# tec_controller_v1.net
KiCad netlist of a schematic drawn in EAGLE
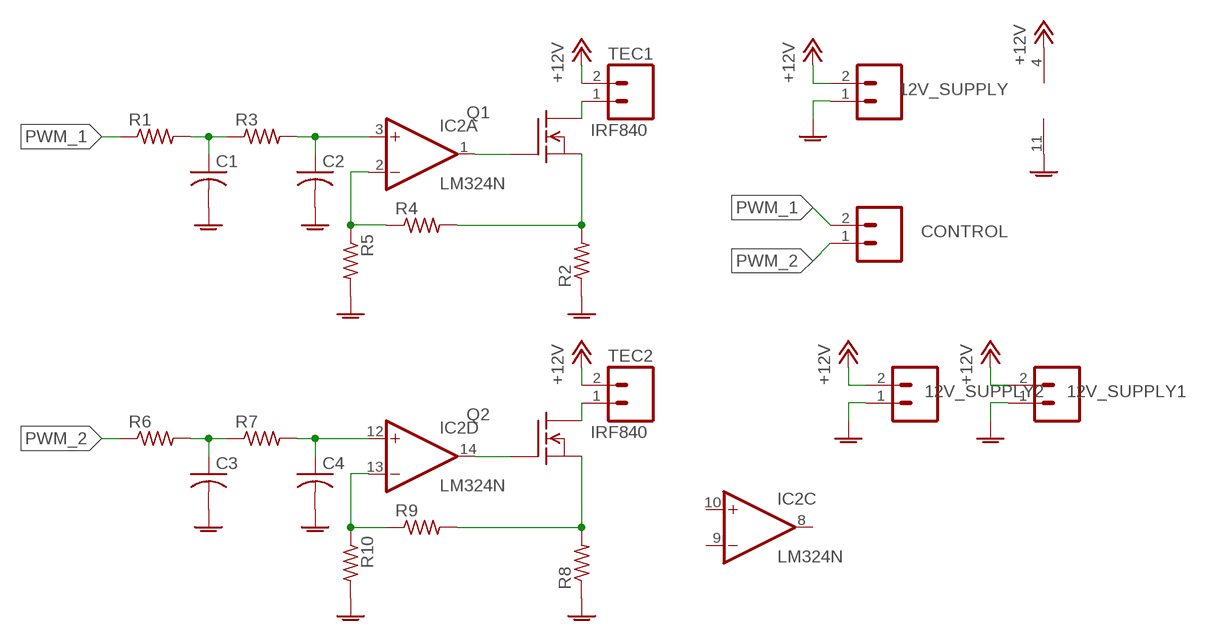
[diagram p0: schematic, sheet 1]

(export (version "E")
  (design (tool "Eeschema 10.0.6"))
  (components
    (comp (ref "12V_SUPPLY")
      (value "M02LOCK_LONGPADS")
      (footprint "eagle-import:1X02_LOCK_LONGPADS")
      (libsource (lib "eagle-import") (part "M02LOCK_LONGPADS"))
    )
    (comp (ref "12V_SUPPLY1")
      (value "M02LOCK_LONGPADS")
      (footprint "eagle-import:1X02_LOCK_LONGPADS")
      (libsource (lib "eagle-import") (part "M02LOCK_LONGPADS"))
    )
    (comp (ref "12V_SUPPLY2")
      (value "M02LOCK_LONGPADS")
      (footprint "eagle-import:1X02_LOCK_LONGPADS")
      (libsource (lib "eagle-import") (part "M02LOCK_LONGPADS"))
    )
    (comp (ref "C1")
      (value "C-USC0805")
      (footprint "eagle-import:C0805")
      (libsource (lib "eagle-import") (part "C-USC0805"))
    )
    (comp (ref "C2")
      (value "C-USC0805")
      (footprint "eagle-import:C0805")
      (libsource (lib "eagle-import") (part "C-USC0805"))
    )
    (comp (ref "C3")
      (value "C-USC0805")
      (footprint "eagle-import:C0805")
      (libsource (lib "eagle-import") (part "C-USC0805"))
    )
    (comp (ref "C4")
      (value "C-USC0805")
      (footprint "eagle-import:C0805")
      (libsource (lib "eagle-import") (part "C-USC0805"))
    )
    (comp (ref "CONTROL")
      (value "M02LOCK_LONGPADS")
      (footprint "eagle-import:1X02_LOCK_LONGPADS")
      (libsource (lib "eagle-import") (part "M02LOCK_LONGPADS"))
    )
    (comp (ref "IC2")
      (value "LM324N")
      (footprint "eagle-import:DIL14")
      (libsource (lib "eagle-import") (part "LM324N"))
    )
    (comp (ref "Q1")
      (value "IRF840")
      (footprint "eagle-import:TO220")
      (libsource (lib "eagle-import") (part "IRF840"))
    )
    (comp (ref "Q2")
      (value "IRF840")
      (footprint "eagle-import:TO220")
      (libsource (lib "eagle-import") (part "IRF840"))
    )
    (comp (ref "R1")
      (value "R-US_M0805")
      (footprint "eagle-import:M0805")
      (libsource (lib "eagle-import") (part "R-US_M0805"))
    )
    (comp (ref "R2")
      (value "R-US_V235/17")
      (footprint "eagle-import:V235_17")
      (libsource (lib "eagle-import") (part "R-US_V235/17"))
    )
    (comp (ref "R3")
      (value "R-US_M0805")
      (footprint "eagle-import:M0805")
      (libsource (lib "eagle-import") (part "R-US_M0805"))
    )
    (comp (ref "R4")
      (value "R-US_M0805")
      (footprint "eagle-import:M0805")
      (libsource (lib "eagle-import") (part "R-US_M0805"))
    )
    (comp (ref "R5")
      (value "R-US_M0805")
      (footprint "eagle-import:M0805")
      (libsource (lib "eagle-import") (part "R-US_M0805"))
    )
    (comp (ref "R6")
      (value "R-US_M0805")
      (footprint "eagle-import:M0805")
      (libsource (lib "eagle-import") (part "R-US_M0805"))
    )
    (comp (ref "R7")
      (value "R-US_M0805")
      (footprint "eagle-import:M0805")
      (libsource (lib "eagle-import") (part "R-US_M0805"))
    )
    (comp (ref "R8")
      (value "R-US_V235/17")
      (footprint "eagle-import:V235_17")
      (libsource (lib "eagle-import") (part "R-US_V235/17"))
    )
    (comp (ref "R9")
      (value "R-US_M0805")
      (footprint "eagle-import:M0805")
      (libsource (lib "eagle-import") (part "R-US_M0805"))
    )
    (comp (ref "R10")
      (value "R-US_M0805")
      (footprint "eagle-import:M0805")
      (libsource (lib "eagle-import") (part "R-US_M0805"))
    )
    (comp (ref "TEC1")
      (value "M02LOCK_LONGPADS")
      (footprint "eagle-import:1X02_LOCK_LONGPADS")
      (libsource (lib "eagle-import") (part "M02LOCK_LONGPADS"))
    )
    (comp (ref "TEC2")
      (value "M02LOCK_LONGPADS")
      (footprint "eagle-import:1X02_LOCK_LONGPADS")
      (libsource (lib "eagle-import") (part "M02LOCK_LONGPADS"))
    )
  )
  (nets
    (net (code "1") (name "+12V") (class "Default")
      (node (ref "12V_SUPPLY") (pin "2") (pinfunction "2_2") (pintype "passive"))
      (node (ref "12V_SUPPLY1") (pin "2") (pinfunction "2_2") (pintype "passive"))
      (node (ref "12V_SUPPLY2") (pin "2") (pinfunction "2_2") (pintype "passive"))
      (node (ref "IC2") (pin "4") (pinfunction "V+_4") (pintype "power_in"))
      (node (ref "TEC1") (pin "2") (pinfunction "2_2") (pintype "passive"))
      (node (ref "TEC2") (pin "2") (pinfunction "2_2") (pintype "passive"))
    )
    (net (code "2") (name "GNDA") (class "Default")
      (node (ref "12V_SUPPLY") (pin "1") (pinfunction "1_1") (pintype "passive"))
      (node (ref "12V_SUPPLY1") (pin "1") (pinfunction "1_1") (pintype "passive"))
      (node (ref "12V_SUPPLY2") (pin "1") (pinfunction "1_1") (pintype "passive"))
      (node (ref "C1") (pin "2") (pinfunction "2_2") (pintype "passive"))
      (node (ref "C2") (pin "2") (pinfunction "2_2") (pintype "passive"))
      (node (ref "C3") (pin "2") (pinfunction "2_2") (pintype "passive"))
      (node (ref "C4") (pin "2") (pinfunction "2_2") (pintype "passive"))
      (node (ref "IC2") (pin "11") (pinfunction "V-_11") (pintype "power_in"))
      (node (ref "R10") (pin "2") (pinfunction "2_2") (pintype "passive"))
      (node (ref "R2") (pin "1") (pinfunction "1_1") (pintype "passive"))
      (node (ref "R5") (pin "2") (pinfunction "2_2") (pintype "passive"))
      (node (ref "R8") (pin "1") (pinfunction "1_1") (pintype "passive"))
    )
    (net (code "3") (name "Net-(C1-Pad1)") (class "Default")
      (node (ref "C1") (pin "1") (pinfunction "1_1") (pintype "passive"))
      (node (ref "R1") (pin "2") (pinfunction "2_2") (pintype "passive"))
      (node (ref "R3") (pin "1") (pinfunction "1_1") (pintype "passive"))
    )
    (net (code "4") (name "Net-(C3-Pad1)") (class "Default")
      (node (ref "C3") (pin "1") (pinfunction "1_1") (pintype "passive"))
      (node (ref "R6") (pin "2") (pinfunction "2_2") (pintype "passive"))
      (node (ref "R7") (pin "1") (pinfunction "1_1") (pintype "passive"))
    )
    (net (code "5") (name "Net-(IC2A-+IN)") (class "Default")
      (node (ref "C2") (pin "1") (pinfunction "1_1") (pintype "passive"))
      (node (ref "IC2") (pin "3") (pinfunction "+IN_3") (pintype "input"))
      (node (ref "R3") (pin "2") (pinfunction "2_2") (pintype "passive"))
    )
    (net (code "6") (name "Net-(IC2A--IN)") (class "Default")
      (node (ref "IC2") (pin "2") (pinfunction "-IN_2") (pintype "input"))
      (node (ref "R4") (pin "1") (pinfunction "1_1") (pintype "passive"))
      (node (ref "R5") (pin "1") (pinfunction "1_1") (pintype "passive"))
    )
    (net (code "7") (name "Net-(IC2A-OUT)") (class "Default")
      (node (ref "IC2") (pin "1") (pinfunction "OUT_1") (pintype "output"))
      (node (ref "Q1") (pin "1") (pinfunction "G_1") (pintype "passive"))
    )
    (net (code "8") (name "Net-(IC2D-+IN)") (class "Default")
      (node (ref "C4") (pin "1") (pinfunction "1_1") (pintype "passive"))
      (node (ref "IC2") (pin "12") (pinfunction "+IN_12") (pintype "input"))
      (node (ref "R7") (pin "2") (pinfunction "2_2") (pintype "passive"))
    )
    (net (code "9") (name "Net-(IC2D--IN)") (class "Default")
      (node (ref "IC2") (pin "13") (pinfunction "-IN_13") (pintype "input"))
      (node (ref "R10") (pin "1") (pinfunction "1_1") (pintype "passive"))
      (node (ref "R9") (pin "1") (pinfunction "1_1") (pintype "passive"))
    )
    (net (code "10") (name "Net-(IC2D-OUT)") (class "Default")
      (node (ref "IC2") (pin "14") (pinfunction "OUT_14") (pintype "output"))
      (node (ref "Q2") (pin "1") (pinfunction "G_1") (pintype "passive"))
    )
    (net (code "11") (name "Net-(Q1-D)") (class "Default")
      (node (ref "Q1") (pin "2") (pinfunction "D_2") (pintype "passive"))
      (node (ref "TEC1") (pin "1") (pinfunction "1_1") (pintype "passive"))
    )
    (net (code "12") (name "Net-(Q1-S)") (class "Default")
      (node (ref "Q1") (pin "3") (pinfunction "S_3") (pintype "passive"))
      (node (ref "R2") (pin "2") (pinfunction "2_2") (pintype "passive"))
      (node (ref "R4") (pin "2") (pinfunction "2_2") (pintype "passive"))
    )
    (net (code "13") (name "Net-(Q2-D)") (class "Default")
      (node (ref "Q2") (pin "2") (pinfunction "D_2") (pintype "passive"))
      (node (ref "TEC2") (pin "1") (pinfunction "1_1") (pintype "passive"))
    )
    (net (code "14") (name "Net-(Q2-S)") (class "Default")
      (node (ref "Q2") (pin "3") (pinfunction "S_3") (pintype "passive"))
      (node (ref "R8") (pin "2") (pinfunction "2_2") (pintype "passive"))
      (node (ref "R9") (pin "2") (pinfunction "2_2") (pintype "passive"))
    )
    (net (code "15") (name "PWM_1") (class "Default")
      (node (ref "CONTROL") (pin "2") (pinfunction "2_2") (pintype "passive"))
      (node (ref "R1") (pin "1") (pinfunction "1_1") (pintype "passive"))
    )
    (net (code "16") (name "PWM_2") (class "Default")
      (node (ref "CONTROL") (pin "1") (pinfunction "1_1") (pintype "passive"))
      (node (ref "R6") (pin "1") (pinfunction "1_1") (pintype "passive"))
    )
    (net (code "17") (name "unconnected-(IC2C-+IN-Pad10)") (class "Default")
      (node (ref "IC2") (pin "10") (pinfunction "+IN_10") (pintype "input"))
    )
    (net (code "18") (name "unconnected-(IC2C--IN-Pad9)") (class "Default")
      (node (ref "IC2") (pin "9") (pinfunction "-IN_9") (pintype "input"))
    )
    (net (code "19") (name "unconnected-(IC2C-OUT-Pad8)") (class "Default")
      (node (ref "IC2") (pin "8") (pinfunction "OUT_8") (pintype "output"))
    )
  )
)
